# tritiled22.net
KiCad netlist of a schematic drawn in EAGLE
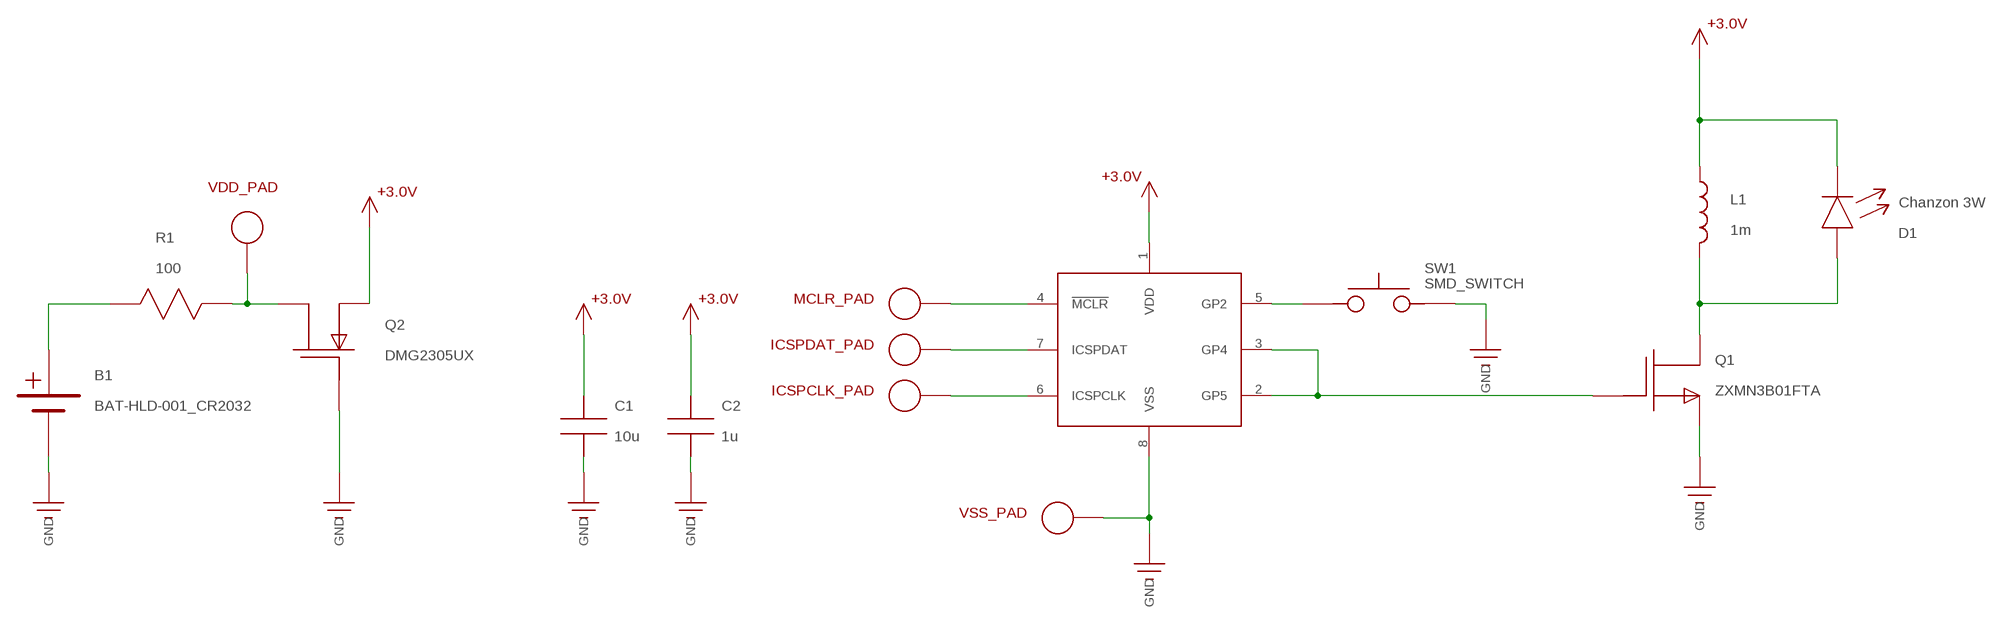
[diagram p0: schematic, sheet 1]

(export (version "E")
  (design (tool "Eeschema 10.0.6"))
  (components
    (comp (ref "B1")
      (value "BAT-HLD-001_CR2032")
      (footprint "eagle-import:CR2032_BAT-HLD_001")
      (libsource (lib "eagle-import") (part "BAT-HLD-001_CR2032"))
    )
    (comp (ref "C1")
      (value "10u")
      (footprint "eagle-import:1206")
      (libsource (lib "eagle-import") (part "C1206"))
    )
    (comp (ref "C2")
      (value "1u")
      (footprint "eagle-import:0805")
      (libsource (lib "eagle-import") (part "C0805"))
    )
    (comp (ref "D1")
      (value "Chanzon 3W")
      (footprint "eagle-import:LED_3W")
      (libsource (lib "eagle-import") (part "LED_3W"))
    )
    (comp (ref "ICSPCLK_PAD")
      (value "ICSP_PAD")
      (footprint "eagle-import:ICSP_PAD")
      (libsource (lib "eagle-import") (part "ICSP_PAD"))
    )
    (comp (ref "ICSPDAT_PAD")
      (value "ICSP_PAD")
      (footprint "eagle-import:ICSP_PAD")
      (libsource (lib "eagle-import") (part "ICSP_PAD"))
    )
    (comp (ref "L1")
      (value "1m")
      (footprint "eagle-import:SRR6028_INDUCTOR")
      (libsource (lib "eagle-import") (part "SRR6028_INDUCTOR"))
    )
    (comp (ref "MCLR_PAD")
      (value "ICSP_PAD")
      (footprint "eagle-import:ICSP_PAD")
      (libsource (lib "eagle-import") (part "ICSP_PAD"))
    )
    (comp (ref "Q1")
      (value "ZXMN3B01FTA")
      (footprint "eagle-import:SOT-23")
      (libsource (lib "eagle-import") (part "ZXMN3B01FSOT23"))
    )
    (comp (ref "Q2")
      (value "DMG2305UX")
      (footprint "eagle-import:SOT-23")
      (libsource (lib "eagle-import") (part "DMG2305UXSOT23"))
    )
    (comp (ref "R1")
      (value "100")
      (footprint "eagle-import:R1206")
      (libsource (lib "eagle-import") (part "R1206"))
    )
    (comp (ref "SW1")
      (value "SMD_SWITCH")
      (footprint "eagle-import:SMD_SWITCH")
      (libsource (lib "eagle-import") (part "SMD_SWITCH"))
    )
    (comp (ref "U1")
      (value "PIC12LF1571")
      (footprint "eagle-import:SOIC8")
      (libsource (lib "eagle-import") (part "PIC12LF1571"))
    )
    (comp (ref "VDD_PAD")
      (value "ICSP_PAD")
      (footprint "eagle-import:ICSP_PAD")
      (libsource (lib "eagle-import") (part "ICSP_PAD"))
    )
    (comp (ref "VSS_PAD")
      (value "ICSP_PAD")
      (footprint "eagle-import:ICSP_PAD")
      (libsource (lib "eagle-import") (part "ICSP_PAD"))
    )
  )
  (nets
    (net (code "1") (name "+3.0V") (class "Default")
      (node (ref "C1") (pin "P$1") (pinfunction "P$1_P$1") (pintype "bidirectional"))
      (node (ref "C2") (pin "P$1") (pinfunction "P$1_P$1") (pintype "bidirectional"))
      (node (ref "D1") (pin "C") (pinfunction "C_C") (pintype "bidirectional"))
      (node (ref "L1") (pin "P$1") (pinfunction "1_P$1") (pintype "passive"))
      (node (ref "Q2") (pin "2") (pinfunction "S_2") (pintype "bidirectional"))
      (node (ref "U1") (pin "1") (pinfunction "VDD_1") (pintype "bidirectional"))
    )
    (net (code "2") (name "GND") (class "Default")
      (node (ref "B1") (pin "GND") (pinfunction "0V_GND") (pintype "power_in"))
      (node (ref "C1") (pin "P$2") (pinfunction "P$2_P$2") (pintype "bidirectional"))
      (node (ref "C2") (pin "P$2") (pinfunction "P$2_P$2") (pintype "bidirectional"))
      (node (ref "Q1") (pin "2") (pinfunction "S_2") (pintype "bidirectional"))
      (node (ref "Q2") (pin "1") (pinfunction "G_1") (pintype "bidirectional"))
      (node (ref "SW1") (pin "P$3") (pinfunction "P$2_P$3") (pintype "bidirectional"))
      (node (ref "SW1") (pin "P$4") (pinfunction "P$2_P$4") (pintype "bidirectional"))
      (node (ref "U1") (pin "8") (pinfunction "VSS_8") (pintype "bidirectional"))
      (node (ref "VSS_PAD") (pin "P$2") (pinfunction "P$1_P$2") (pintype "bidirectional"))
    )
    (net (code "3") (name "Net-(B1-+V-Pad+V1)") (class "Default")
      (node (ref "B1") (pin "+V1") (pinfunction "+V_+V1") (pintype "power_in"))
      (node (ref "B1") (pin "+V2") (pinfunction "+V_+V2") (pintype "power_in"))
      (node (ref "R1") (pin "P$1") (pinfunction "P$1_P$1") (pintype "bidirectional"))
    )
    (net (code "4") (name "Net-(ICSPCLK_PAD-P$1)") (class "Default")
      (node (ref "ICSPCLK_PAD") (pin "P$2") (pinfunction "P$1_P$2") (pintype "bidirectional"))
      (node (ref "U1") (pin "6") (pinfunction "ICSPCLK_6") (pintype "bidirectional"))
    )
    (net (code "5") (name "Net-(ICSPDAT_PAD-P$1)") (class "Default")
      (node (ref "ICSPDAT_PAD") (pin "P$2") (pinfunction "P$1_P$2") (pintype "bidirectional"))
      (node (ref "U1") (pin "7") (pinfunction "ICSPDAT_7") (pintype "bidirectional"))
    )
    (net (code "6") (name "Net-(L1-2)") (class "Default")
      (node (ref "D1") (pin "A") (pinfunction "A_A") (pintype "bidirectional"))
      (node (ref "L1") (pin "P$2") (pinfunction "2_P$2") (pintype "passive"))
      (node (ref "Q1") (pin "3") (pinfunction "D_3") (pintype "bidirectional"))
    )
    (net (code "7") (name "Net-(MCLR_PAD-P$1)") (class "Default")
      (node (ref "MCLR_PAD") (pin "P$2") (pinfunction "P$1_P$2") (pintype "bidirectional"))
      (node (ref "U1") (pin "4") (pinfunction "~{MCLR}_4") (pintype "bidirectional"))
    )
    (net (code "8") (name "Net-(Q1-G)") (class "Default")
      (node (ref "Q1") (pin "1") (pinfunction "G_1") (pintype "bidirectional"))
      (node (ref "U1") (pin "2") (pinfunction "GP5_2") (pintype "bidirectional"))
      (node (ref "U1") (pin "3") (pinfunction "GP4_3") (pintype "bidirectional"))
    )
    (net (code "9") (name "Net-(Q2-D)") (class "Default")
      (node (ref "Q2") (pin "3") (pinfunction "D_3") (pintype "bidirectional"))
      (node (ref "R1") (pin "P$2") (pinfunction "P$2_P$2") (pintype "bidirectional"))
      (node (ref "VDD_PAD") (pin "P$2") (pinfunction "P$1_P$2") (pintype "bidirectional"))
    )
    (net (code "10") (name "Net-(U1-GP2)") (class "Default")
      (node (ref "SW1") (pin "P$1") (pinfunction "P$1_P$1") (pintype "bidirectional"))
      (node (ref "SW1") (pin "P$2") (pinfunction "P$1_P$2") (pintype "bidirectional"))
      (node (ref "U1") (pin "5") (pinfunction "GP2_5") (pintype "bidirectional"))
    )
  )
)
